# LT3790.net
KiCad netlist of a schematic drawn in Altium Designer
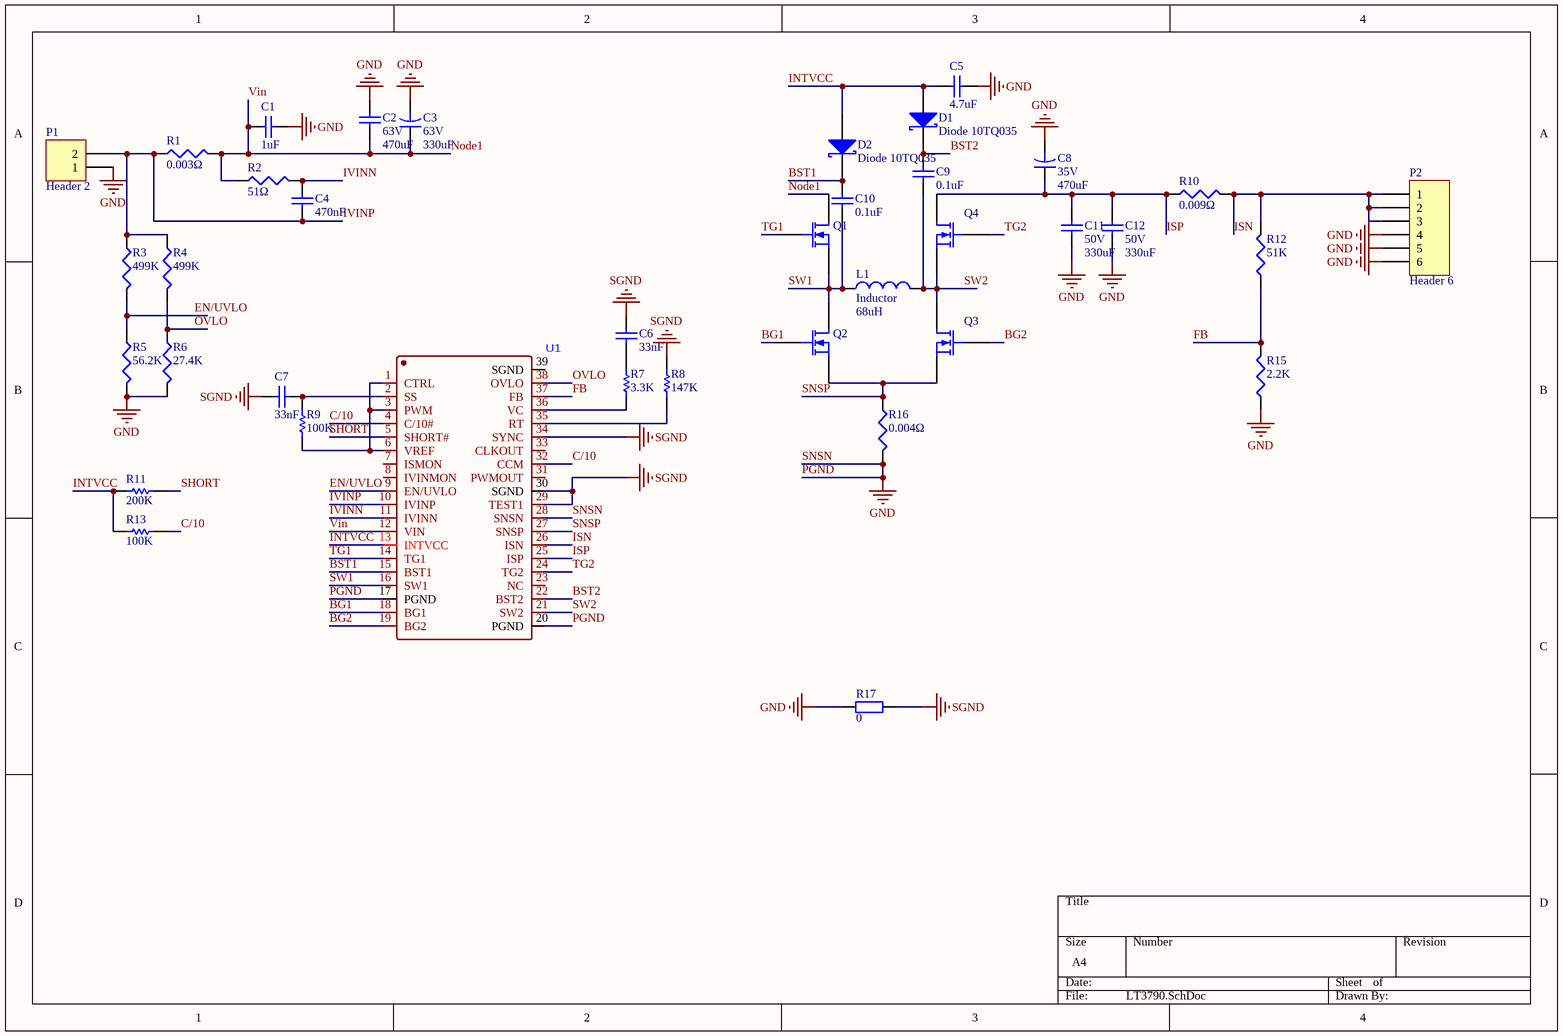
[diagram p0: LT3790.SchDoc]

(export (version "E")
  (design (tool "Eeschema 10.0.6"))
  (components
    (comp (ref "C1")
      (value "1uF")
      (footprint "CAP0603")
      (description "0603")
      (fields (field (name "PUBLISHER") "Altium Limited"))
      (libsource (lib "Miscellaneous Devices") (part "Cap"))
    )
    (comp (ref "C2")
      (value "63V")
      (footprint "CAP-SMD_D16xl 16.5mm")
      (description "SMD D16xl")
      (fields (field (name "ALTIUM_VALUE") "470uF") (field (name "PUBLISHER") "Altium Limited"))
      (libsource (lib "Miscellaneous Devices") (part "Cap"))
    )
    (comp (ref "C3")
      (value "63V")
      (footprint "CAP-SMD_D16xl 16.5mm")
      (description "SMD,D16xl")
      (fields (field (name "ALTIUM_VALUE") "330uF") (field (name "PUBLISHER") "Altium Limited"))
      (libsource (lib "Miscellaneous Devices") (part "Cap2"))
    )
    (comp (ref "C4")
      (value "470nF")
      (footprint "cap0402")
      (description "0402")
      (fields (field (name "PUBLISHER") "Altium Limited"))
      (libsource (lib "Miscellaneous Devices") (part "Cap"))
    )
    (comp (ref "C5")
      (value "4.7uF")
      (footprint "CAP0603")
      (description "0603")
      (fields (field (name "PUBLISHER") "Altium Limited"))
      (libsource (lib "Miscellaneous Devices") (part "Cap"))
    )
    (comp (ref "C6")
      (value "33nF")
      (footprint "cap0402")
      (description "0402")
      (fields (field (name "PUBLISHER") "Altium Limited"))
      (libsource (lib "Miscellaneous Devices") (part "Cap"))
    )
    (comp (ref "C7")
      (value "33nF")
      (footprint "cap0402")
      (description "0402")
      (fields (field (name "PUBLISHER") "Altium Limited"))
      (libsource (lib "Miscellaneous Devices") (part "Cap"))
    )
    (comp (ref "C8")
      (value "35V")
      (footprint "SMD,D10xl10.5mm")
      (description "RVT470UF35V67RV0056")
      (fields (field (name "ALTIUM_VALUE") "470uF") (field (name "PUBLISHER") "Altium Limited"))
      (libsource (lib "Miscellaneous Devices") (part "Cap2"))
    )
    (comp (ref "C9")
      (value "0.1uF")
      (footprint "CAP0603")
      (description "0603")
      (fields (field (name "PUBLISHER") "Altium Limited"))
      (libsource (lib "Miscellaneous Devices") (part "Cap"))
    )
    (comp (ref "C10")
      (value "0.1uF")
      (footprint "CAP0603")
      (description "0603")
      (fields (field (name "PUBLISHER") "Altium Limited"))
      (libsource (lib "Miscellaneous Devices") (part "Cap"))
    )
    (comp (ref "C11")
      (value "50V")
      (footprint "CAP-SMD,D10xl10.5mm")
      (description "VHTE1051V331MVTMCG")
      (fields (field (name "ALTIUM_VALUE") "330uF") (field (name "PUBLISHER") "Altium Limited"))
      (libsource (lib "Miscellaneous Devices") (part "Cap"))
    )
    (comp (ref "C12")
      (value "50V")
      (footprint "CAP-SMD,D10xl10.5mm")
      (description "0603")
      (fields (field (name "ALTIUM_VALUE") "330uF") (field (name "PUBLISHER") "Altium Limited"))
      (libsource (lib "Miscellaneous Devices") (part "Cap"))
    )
    (comp (ref "D1")
      (value "Diode 10TQ035")
      (footprint "LED-SMB")
      (description "SMBJ5340B")
      (fields (field (name "PUBLISHER") "Altium Limited"))
      (libsource (lib "Miscellaneous Devices") (part "Diode 10TQ035"))
    )
    (comp (ref "D2")
      (value "Diode 10TQ035")
      (footprint "LED-SMB")
      (description "SMBJ5340B")
      (fields (field (name "PUBLISHER") "Altium Limited"))
      (libsource (lib "Miscellaneous Devices") (part "Diode 10TQ035"))
    )
    (comp (ref "L1")
      (value "Inductor")
      (footprint "IND-SMD_L6.0-W6.0")
      (description "SWPA6045S680MT")
      (fields (field (name "ALTIUM_VALUE") "68uH") (field (name "PUBLISHER") "Altium Limited"))
      (libsource (lib "Miscellaneous Devices") (part "Inductor"))
    )
    (comp (ref "P1")
      (value "Header 2")
      (footprint "XT30-M")
      (description "Header, 2-Pin")
      (fields (field (name "PUBLISHER") "Altium Limited"))
      (libsource (lib "Miscellaneous Connectors") (part "Header 2"))
    )
    (comp (ref "P2")
      (value "Header 6")
      (footprint "HDR-M-2.54_2X3")
      (description "Header, 6-Pin")
      (fields (field (name "PUBLISHER") "Altium Limited"))
      (libsource (lib "Miscellaneous Connectors") (part "Header 6"))
    )
    (comp (ref "Q1")
      (value "~")
      (footprint "N-mos TO-252")
      (description "SM4132T9RL")
      (fields (field (name "PUBLISHER") "Altium Limited"))
      (libsource (lib "Miscellaneous Devices") (part "MOSFET-N"))
    )
    (comp (ref "Q2")
      (value "~")
      (footprint "N-mos TO-252")
      (description "N-Channel MOSFET")
      (fields (field (name "PUBLISHER") "Altium Limited"))
      (libsource (lib "Miscellaneous Devices") (part "MOSFET-N"))
    )
    (comp (ref "Q3")
      (value "~")
      (footprint "N-mos TO-252")
      (description "N-Channel MOSFET")
      (fields (field (name "PUBLISHER") "Altium Limited"))
      (libsource (lib "Miscellaneous Devices") (part "MOSFET-N"))
    )
    (comp (ref "Q4")
      (value "~")
      (footprint "N-mos TO-252")
      (description "N-Channel MOSFET")
      (fields (field (name "PUBLISHER") "Altium Limited"))
      (libsource (lib "Miscellaneous Devices") (part "MOSFET-N"))
    )
    (comp (ref "R1")
      (value "0.003Ω")
      (footprint "RES2512")
      (description "2512")
      (fields (field (name "PUBLISHER") "Altium Limited"))
      (libsource (lib "Miscellaneous Devices") (part "Res3"))
    )
    (comp (ref "R2")
      (value "51Ω")
      (footprint "RES0603")
      (description "0603")
      (fields (field (name "PUBLISHER") "Altium Limited"))
      (libsource (lib "Miscellaneous Devices") (part "Res3"))
    )
    (comp (ref "R3")
      (value "499K")
      (footprint "res0402")
      (description "0402")
      (fields (field (name "PUBLISHER") "Altium Limited"))
      (libsource (lib "Miscellaneous Devices") (part "Res3"))
    )
    (comp (ref "R4")
      (value "499K")
      (footprint "res0402")
      (description "0402")
      (fields (field (name "PUBLISHER") "Altium Limited"))
      (libsource (lib "Miscellaneous Devices") (part "Res3"))
    )
    (comp (ref "R5")
      (value "56.2K")
      (footprint "res0402")
      (description "0402")
      (fields (field (name "PUBLISHER") "Altium Limited"))
      (libsource (lib "Miscellaneous Devices") (part "Res3"))
    )
    (comp (ref "R6")
      (value "27.4K")
      (footprint "res0402")
      (description "0402")
      (fields (field (name "PUBLISHER") "Altium Limited"))
      (libsource (lib "Miscellaneous Devices") (part "Res3"))
    )
    (comp (ref "R7")
      (value "3.3K")
      (footprint "res0402")
      (description "0402")
      (fields (field (name "PUBLISHER") "Altium Limited"))
      (libsource (lib "Miscellaneous Devices") (part "Res1"))
    )
    (comp (ref "R8")
      (value "147K")
      (footprint "res0402")
      (description "0402")
      (fields (field (name "PUBLISHER") "Altium Limited"))
      (libsource (lib "Miscellaneous Devices") (part "Res1"))
    )
    (comp (ref "R9")
      (value "100K")
      (footprint "res0402")
      (description "0402")
      (fields (field (name "PUBLISHER") "Altium Limited"))
      (libsource (lib "Miscellaneous Devices") (part "Res1"))
    )
    (comp (ref "R10")
      (value "0.009Ω")
      (footprint "RES2512")
      (description "2512")
      (fields (field (name "PUBLISHER") "Altium Limited"))
      (libsource (lib "Miscellaneous Devices") (part "Res3"))
    )
    (comp (ref "R11")
      (value "200K")
      (footprint "res0402")
      (description "0402")
      (fields (field (name "PUBLISHER") "Altium Limited"))
      (libsource (lib "Miscellaneous Devices") (part "Res1"))
    )
    (comp (ref "R12")
      (value "51K")
      (footprint "res0402")
      (description "0402")
      (fields (field (name "PUBLISHER") "Altium Limited"))
      (libsource (lib "Miscellaneous Devices") (part "Res3"))
    )
    (comp (ref "R13")
      (value "100K")
      (footprint "res0402")
      (description "0402")
      (fields (field (name "PUBLISHER") "Altium Limited"))
      (libsource (lib "Miscellaneous Devices") (part "Res1"))
    )
    (comp (ref "R15")
      (value "2.2K")
      (footprint "res0402")
      (description "0402")
      (fields (field (name "PUBLISHER") "Altium Limited"))
      (libsource (lib "Miscellaneous Devices") (part "Res3"))
    )
    (comp (ref "R16")
      (value "0.004Ω")
      (footprint "RES2512")
      (description "2512")
      (fields (field (name "PUBLISHER") "Altium Limited"))
      (libsource (lib "Miscellaneous Devices") (part "Res3"))
    )
    (comp (ref "R17")
      (value "0")
      (footprint "RES0805")
      (description "0805")
      (fields (field (name "PUBLISHER") "Altium Limited"))
      (libsource (lib "Miscellaneous Devices") (part "Res2"))
    )
    (comp (ref "U1")
      (value "~")
      (footprint "LT3790")
      (libsource (lib "altium-import") (part "root_0_LT3790EFE#PBF_"))
    )
  )
  (nets
    (net (code "1") (name "/BG1") (class "Default")
      (node (ref "Q2") (pin "2") (pinfunction "G_2") (pintype "passive"))
      (node (ref "U1") (pin "18") (pinfunction "BG1_18") (pintype "passive"))
    )
    (net (code "2") (name "/BG2") (class "Default")
      (node (ref "Q3") (pin "2") (pinfunction "G_2") (pintype "passive"))
      (node (ref "U1") (pin "19") (pinfunction "BG2_19") (pintype "passive"))
    )
    (net (code "3") (name "/BST1") (class "Default")
      (node (ref "C10") (pin "1") (pinfunction "1_1") (pintype "passive"))
      (node (ref "D2") (pin "1") (pinfunction "K_1") (pintype "passive"))
      (node (ref "U1") (pin "15") (pinfunction "BST1_15") (pintype "passive"))
    )
    (net (code "4") (name "/BST2") (class "Default")
      (node (ref "C9") (pin "1") (pinfunction "1_1") (pintype "passive"))
      (node (ref "D1") (pin "1") (pinfunction "K_1") (pintype "passive"))
      (node (ref "U1") (pin "22") (pinfunction "BST2_22") (pintype "passive"))
    )
    (net (code "5") (name "/C{slash}10") (class "Default")
      (node (ref "R13") (pin "1") (pinfunction "1_1") (pintype "passive"))
      (node (ref "U1") (pin "32") (pinfunction "CCM_32") (pintype "passive"))
      (node (ref "U1") (pin "4") (pinfunction "C/10#_4") (pintype "passive"))
    )
    (net (code "6") (name "/EN{slash}UVLO") (class "Default")
      (node (ref "R3") (pin "2") (pinfunction "2_2") (pintype "passive"))
      (node (ref "R5") (pin "1") (pinfunction "1_1") (pintype "passive"))
      (node (ref "U1") (pin "9") (pinfunction "EN/UVLO_9") (pintype "passive"))
    )
    (net (code "7") (name "/FB") (class "Default")
      (node (ref "R12") (pin "1") (pinfunction "1_1") (pintype "passive"))
      (node (ref "R15") (pin "2") (pinfunction "2_2") (pintype "passive"))
      (node (ref "U1") (pin "37") (pinfunction "FB_37") (pintype "passive"))
    )
    (net (code "8") (name "/INTVCC") (class "Default")
      (node (ref "C5") (pin "2") (pinfunction "2_2") (pintype "passive"))
      (node (ref "D1") (pin "3") (pinfunction "A_3") (pintype "passive"))
      (node (ref "D2") (pin "3") (pinfunction "A_3") (pintype "passive"))
      (node (ref "R11") (pin "2") (pinfunction "2_2") (pintype "passive"))
      (node (ref "R13") (pin "2") (pinfunction "2_2") (pintype "passive"))
      (node (ref "U1") (pin "13") (pinfunction "INTVCC_13") (pintype "passive"))
    )
    (net (code "9") (name "/ISN") (class "Default")
      (node (ref "P2") (pin "1") (pinfunction "1_1") (pintype "passive"))
      (node (ref "P2") (pin "2") (pinfunction "2_2") (pintype "passive"))
      (node (ref "P2") (pin "3") (pinfunction "3_3") (pintype "passive"))
      (node (ref "R10") (pin "2") (pinfunction "2_2") (pintype "passive"))
      (node (ref "R12") (pin "2") (pinfunction "2_2") (pintype "passive"))
      (node (ref "U1") (pin "26") (pinfunction "ISN_26") (pintype "passive"))
    )
    (net (code "10") (name "/ISP") (class "Default")
      (node (ref "C11") (pin "1") (pinfunction "1_1") (pintype "passive"))
      (node (ref "C12") (pin "1") (pinfunction "1_1") (pintype "passive"))
      (node (ref "C8") (pin "1") (pinfunction "1_1") (pintype "passive"))
      (node (ref "Q4") (pin "1") (pinfunction "D_1") (pintype "passive"))
      (node (ref "R10") (pin "1") (pinfunction "1_1") (pintype "passive"))
      (node (ref "U1") (pin "25") (pinfunction "ISP_25") (pintype "passive"))
    )
    (net (code "11") (name "/IVINN") (class "Default")
      (node (ref "C4") (pin "1") (pinfunction "1_1") (pintype "passive"))
      (node (ref "R2") (pin "2") (pinfunction "2_2") (pintype "passive"))
      (node (ref "U1") (pin "11") (pinfunction "IVINN_11") (pintype "passive"))
    )
    (net (code "12") (name "/IVINP") (class "Default")
      (node (ref "C4") (pin "2") (pinfunction "2_2") (pintype "passive"))
      (node (ref "P1") (pin "2") (pinfunction "2_2") (pintype "passive"))
      (node (ref "R1") (pin "1") (pinfunction "1_1") (pintype "passive"))
      (node (ref "R3") (pin "1") (pinfunction "1_1") (pintype "passive"))
      (node (ref "R4") (pin "1") (pinfunction "1_1") (pintype "passive"))
      (node (ref "U1") (pin "10") (pinfunction "IVINP_10") (pintype "passive"))
    )
    (net (code "13") (name "/Node1") (class "Default")
      (node (ref "C1") (pin "2") (pinfunction "2_2") (pintype "passive"))
      (node (ref "C2") (pin "1") (pinfunction "1_1") (pintype "passive"))
      (node (ref "C3") (pin "1") (pinfunction "1_1") (pintype "passive"))
      (node (ref "Q1") (pin "1") (pinfunction "D_1") (pintype "passive"))
      (node (ref "R1") (pin "2") (pinfunction "2_2") (pintype "passive"))
      (node (ref "R2") (pin "1") (pinfunction "1_1") (pintype "passive"))
      (node (ref "U1") (pin "12") (pinfunction "VIN_12") (pintype "passive"))
    )
    (net (code "14") (name "/OVLO") (class "Default")
      (node (ref "R4") (pin "2") (pinfunction "2_2") (pintype "passive"))
      (node (ref "R6") (pin "1") (pinfunction "1_1") (pintype "passive"))
      (node (ref "U1") (pin "38") (pinfunction "OVLO_38") (pintype "passive"))
    )
    (net (code "15") (name "/SHORT") (class "Default")
      (node (ref "R11") (pin "1") (pinfunction "1_1") (pintype "passive"))
      (node (ref "U1") (pin "5") (pinfunction "SHORT#_5") (pintype "passive"))
    )
    (net (code "16") (name "/SNSP") (class "Default")
      (node (ref "Q2") (pin "3") (pinfunction "S_3") (pintype "passive"))
      (node (ref "Q3") (pin "3") (pinfunction "S_3") (pintype "passive"))
      (node (ref "R16") (pin "1") (pinfunction "1_1") (pintype "passive"))
      (node (ref "U1") (pin "27") (pinfunction "SNSP_27") (pintype "passive"))
    )
    (net (code "17") (name "/SW1") (class "Default")
      (node (ref "C10") (pin "2") (pinfunction "2_2") (pintype "passive"))
      (node (ref "L1") (pin "1") (pinfunction "1_1") (pintype "passive"))
      (node (ref "Q1") (pin "3") (pinfunction "S_3") (pintype "passive"))
      (node (ref "Q2") (pin "1") (pinfunction "D_1") (pintype "passive"))
      (node (ref "U1") (pin "16") (pinfunction "SW1_16") (pintype "passive"))
    )
    (net (code "18") (name "/SW2") (class "Default")
      (node (ref "C9") (pin "2") (pinfunction "2_2") (pintype "passive"))
      (node (ref "L1") (pin "2") (pinfunction "2_2") (pintype "passive"))
      (node (ref "Q3") (pin "1") (pinfunction "D_1") (pintype "passive"))
      (node (ref "Q4") (pin "3") (pinfunction "S_3") (pintype "passive"))
      (node (ref "U1") (pin "21") (pinfunction "SW2_21") (pintype "passive"))
    )
    (net (code "19") (name "/TG1") (class "Default")
      (node (ref "Q1") (pin "2") (pinfunction "G_2") (pintype "passive"))
      (node (ref "U1") (pin "14") (pinfunction "TG1_14") (pintype "passive"))
    )
    (net (code "20") (name "/TG2") (class "Default")
      (node (ref "Q4") (pin "2") (pinfunction "G_2") (pintype "passive"))
      (node (ref "U1") (pin "24") (pinfunction "TG2_24") (pintype "passive"))
    )
    (net (code "21") (name "GND") (class "Default")
      (node (ref "C1") (pin "1") (pinfunction "1_1") (pintype "passive"))
      (node (ref "C11") (pin "2") (pinfunction "2_2") (pintype "passive"))
      (node (ref "C12") (pin "2") (pinfunction "2_2") (pintype "passive"))
      (node (ref "C2") (pin "2") (pinfunction "2_2") (pintype "passive"))
      (node (ref "C3") (pin "2") (pinfunction "2_2") (pintype "passive"))
      (node (ref "C5") (pin "1") (pinfunction "1_1") (pintype "passive"))
      (node (ref "C8") (pin "2") (pinfunction "2_2") (pintype "passive"))
      (node (ref "P1") (pin "1") (pinfunction "1_1") (pintype "passive"))
      (node (ref "P2") (pin "4") (pinfunction "4_4") (pintype "passive"))
      (node (ref "P2") (pin "5") (pinfunction "5_5") (pintype "passive"))
      (node (ref "P2") (pin "6") (pinfunction "6_6") (pintype "passive"))
      (node (ref "R15") (pin "1") (pinfunction "1_1") (pintype "passive"))
      (node (ref "R16") (pin "2") (pinfunction "2_2") (pintype "passive"))
      (node (ref "R17") (pin "1") (pinfunction "1_1") (pintype "passive"))
      (node (ref "R5") (pin "2") (pinfunction "2_2") (pintype "passive"))
      (node (ref "R6") (pin "2") (pinfunction "2_2") (pintype "passive"))
      (node (ref "U1") (pin "17") (pinfunction "PGND_17") (pintype "passive"))
      (node (ref "U1") (pin "20") (pinfunction "PGND_20") (pintype "passive"))
      (node (ref "U1") (pin "28") (pinfunction "SNSN_28") (pintype "passive"))
    )
    (net (code "22") (name "Net-(C6-Pad2)") (class "Default")
      (node (ref "C6") (pin "2") (pinfunction "2_2") (pintype "passive"))
      (node (ref "R7") (pin "1") (pinfunction "1_1") (pintype "passive"))
    )
    (net (code "23") (name "Net-(U1-CTRL)") (class "Default")
      (node (ref "R9") (pin "1") (pinfunction "1_1") (pintype "passive"))
      (node (ref "U1") (pin "1") (pinfunction "CTRL_1") (pintype "passive"))
      (node (ref "U1") (pin "3") (pinfunction "PWM_3") (pintype "passive"))
      (node (ref "U1") (pin "6") (pinfunction "VREF_6") (pintype "passive"))
    )
    (net (code "24") (name "Net-(U1-RT)") (class "Default")
      (node (ref "R8") (pin "2") (pinfunction "2_2") (pintype "passive"))
      (node (ref "U1") (pin "35") (pinfunction "RT_35") (pintype "passive"))
    )
    (net (code "25") (name "Net-(U1-SS)") (class "Default")
      (node (ref "C7") (pin "1") (pinfunction "1_1") (pintype "passive"))
      (node (ref "R9") (pin "2") (pinfunction "2_2") (pintype "passive"))
      (node (ref "U1") (pin "2") (pinfunction "SS_2") (pintype "passive"))
    )
    (net (code "26") (name "Net-(U1-VC)") (class "Default")
      (node (ref "R7") (pin "2") (pinfunction "2_2") (pintype "passive"))
      (node (ref "U1") (pin "36") (pinfunction "VC_36") (pintype "passive"))
    )
    (net (code "27") (name "SGND") (class "Default")
      (node (ref "C6") (pin "1") (pinfunction "1_1") (pintype "passive"))
      (node (ref "C7") (pin "2") (pinfunction "2_2") (pintype "passive"))
      (node (ref "R17") (pin "2") (pinfunction "2_2") (pintype "passive"))
      (node (ref "R8") (pin "1") (pinfunction "1_1") (pintype "passive"))
      (node (ref "U1") (pin "29") (pinfunction "TEST1_29") (pintype "passive"))
      (node (ref "U1") (pin "30") (pinfunction "SGND_30") (pintype "passive"))
      (node (ref "U1") (pin "34") (pinfunction "SYNC_34") (pintype "passive"))
    )
    (net (code "28") (name "unconnected-(U1-CLKOUT-Pad33)") (class "Default")
      (node (ref "U1") (pin "33") (pinfunction "CLKOUT_33") (pintype "passive"))
    )
    (net (code "29") (name "unconnected-(U1-ISMON-Pad7)") (class "Default")
      (node (ref "U1") (pin "7") (pinfunction "ISMON_7") (pintype "passive"))
    )
    (net (code "30") (name "unconnected-(U1-IVINMON-Pad8)") (class "Default")
      (node (ref "U1") (pin "8") (pinfunction "IVINMON_8") (pintype "passive"))
    )
    (net (code "31") (name "unconnected-(U1-NC-Pad23)") (class "Default")
      (node (ref "U1") (pin "23") (pinfunction "NC_23") (pintype "passive"))
    )
    (net (code "32") (name "unconnected-(U1-PWMOUT-Pad31)") (class "Default")
      (node (ref "U1") (pin "31") (pinfunction "PWMOUT_31") (pintype "passive"))
    )
    (net (code "33") (name "unconnected-(U1-SGND-Pad39)") (class "Default")
      (node (ref "U1") (pin "39") (pinfunction "SGND_39") (pintype "passive"))
    )
  )
)
